# RAK3162_SX1262.net
KiCad netlist of a schematic drawn in Altium Designer
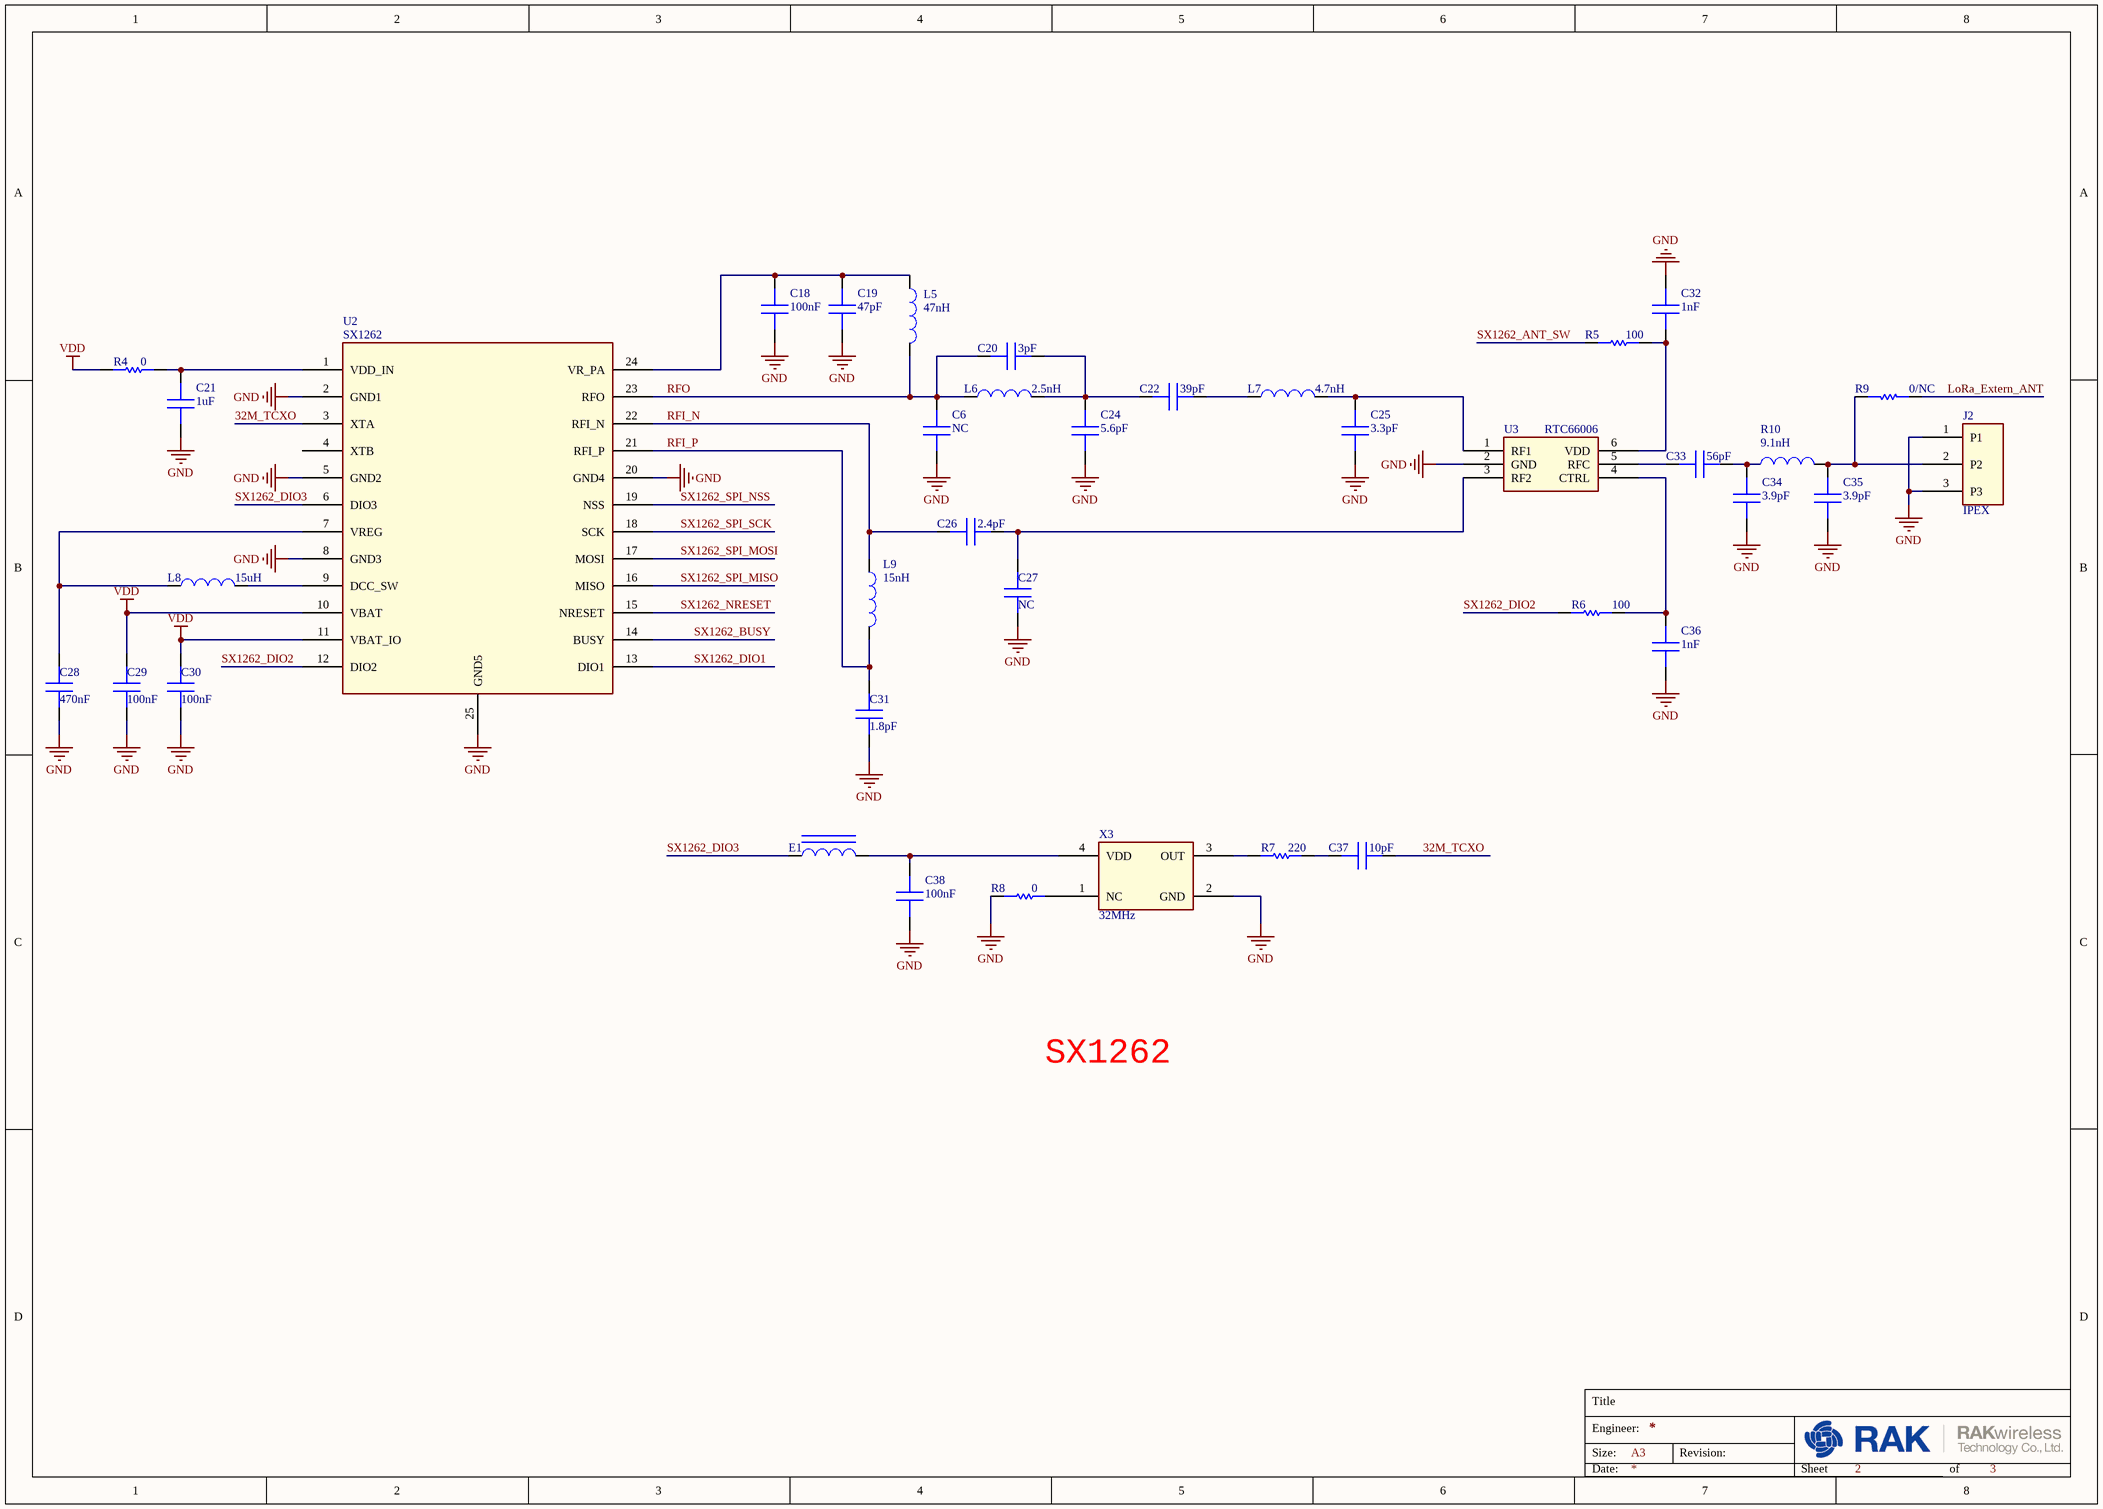
[diagram p0: RAK3162_SX1262.SchDoc]

(export (version "E")
  (design (tool "Eeschema 10.0.6"))
  (components
    (comp (ref "C6")
      (value "NC")
      (footprint "sc0201")
      (description "Capacitor-50V-5.6pF-±0.25pF-COG-0201")
      (fields (field (name "MANUFACTURER") "MURATA") (field (name "TOLERANCE") "±0.25pF"))
      (libsource (lib "RAK_Database_Lib_2022") (part "CAPACITOR NP"))
    )
    (comp (ref "C18")
      (value "100nF")
      (footprint "sc0201")
      (description "Capacitor-6.3V-100nF-±10%-X5R-0201")
      (fields (field (name "MANUFACTURER") "YAGEO") (field (name "TOLERANCE") "±10%"))
      (libsource (lib "RAK_Database_Lib_2022") (part "CAPACITOR NP"))
    )
    (comp (ref "C19")
      (value "47pF")
      (footprint "sc0201")
      (description "Capacitor-25V-47pF-±5%-NPO-0201")
      (fields (field (name "MANUFACTURER") "YAGEO") (field (name "TOLERANCE") "±5%"))
      (libsource (lib "RAK_Database_Lib_2022") (part "CAPACITOR NP"))
    )
    (comp (ref "C20")
      (value "3pF")
      (footprint "sc0201")
      (description "Capacitor-50V-3pF-±0.25pF-NPO-0201")
      (fields (field (name "MANUFACTURER") "YAGEO") (field (name "TOLERANCE") "±0.25pF"))
      (libsource (lib "RAK_Database_Lib_2022") (part "CAPACITOR NP"))
    )
    (comp (ref "C21")
      (value "1uF")
      (footprint "sc0201")
      (description "Capacitor-6.3V-1uF-±20%-X5R-0201")
      (fields (field (name "MANUFACTURER") "YAGEO") (field (name "TOLERANCE") "±20%"))
      (libsource (lib "RAK_Database_Lib_2022") (part "CAPACITOR NP"))
    )
    (comp (ref "C22")
      (value "39pF")
      (footprint "sc0201")
      (description "Capacitor-25V-39pF-±5%-NPO-0201")
      (fields (field (name "MANUFACTURER") "YAGEO") (field (name "TOLERANCE") "±5%"))
      (libsource (lib "RAK_Database_Lib_2022") (part "CAPACITOR NP"))
    )
    (comp (ref "C24")
      (value "5.6pF")
      (footprint "sc0201")
      (description "Capacitor-50V-5.6pF-±0.25pF-COG-0201")
      (fields (field (name "MANUFACTURER") "MURATA") (field (name "TOLERANCE") "±0.25pF"))
      (libsource (lib "RAK_Database_Lib_2022") (part "CAPACITOR NP"))
    )
    (comp (ref "C25")
      (value "3.3pF")
      (footprint "sc0201")
      (description "Capacitor-50V-3.3pF-±0.25pF-NPO-0201")
      (fields (field (name "MANUFACTURER") "YAGEO") (field (name "TOLERANCE") "±0.25pF"))
      (libsource (lib "RAK_Database_Lib_2022") (part "CAPACITOR NP"))
    )
    (comp (ref "C26")
      (value "2.4pF")
      (footprint "sc0201")
      (description "Capacitor-50V-2.4pF-±0.25pF-NPO-0201")
      (fields (field (name "MANUFACTURER") "YAGEO") (field (name "TOLERANCE") "±0.25pF"))
      (libsource (lib "RAK_Database_Lib_2022") (part "CAPACITOR NP"))
    )
    (comp (ref "C27")
      (value "NC")
      (footprint "sc0201")
      (description "Capacitor-25V-47pF-±5%-NPO-0201")
      (fields (field (name "MANUFACTURER") "YAGEO") (field (name "TOLERANCE") "±5%"))
      (libsource (lib "RAK_Database_Lib_2022") (part "CAPACITOR NP"))
    )
    (comp (ref "C28")
      (value "470nF")
      (footprint "sc0201")
      (description "Capacitor-6.3V-470nF-±20%-X5R-0201")
      (fields (field (name "MANUFACTURER") "MURATA") (field (name "TOLERANCE") "±20%"))
      (libsource (lib "RAK_Database_Lib_2022") (part "CAPACITOR NP"))
    )
    (comp (ref "C29")
      (value "100nF")
      (footprint "sc0201")
      (description "Capacitor-6.3V-100nF-±10%-X5R-0201")
      (fields (field (name "MANUFACTURER") "YAGEO") (field (name "TOLERANCE") "±10%"))
      (libsource (lib "RAK_Database_Lib_2022") (part "CAPACITOR NP"))
    )
    (comp (ref "C30")
      (value "100nF")
      (footprint "sc0201")
      (description "Capacitor-6.3V-100nF-±10%-X5R-0201")
      (fields (field (name "MANUFACTURER") "YAGEO") (field (name "TOLERANCE") "±10%"))
      (libsource (lib "RAK_Database_Lib_2022") (part "CAPACITOR NP"))
    )
    (comp (ref "C31")
      (value "1.8pF")
      (footprint "sc0201")
      (description "Capacitor-50V-1.8pF-±0.25pF-NPO-0201")
      (fields (field (name "MANUFACTURER") "YAGEO") (field (name "TOLERANCE") "±0.25pF"))
      (libsource (lib "RAK_Database_Lib_2022") (part "CAPACITOR NP"))
    )
    (comp (ref "C32")
      (value "1nF")
      (footprint "sc0201")
      (description "Capacitor-25V-1nF-±10%-X7R-0201")
      (fields (field (name "MANUFACTURER") "YAGEO") (field (name "TOLERANCE") "±10%"))
      (libsource (lib "RAK_Database_Lib_2022") (part "CAPACITOR NP"))
    )
    (comp (ref "C33")
      (value "56pF")
      (footprint "sc0201")
      (description "Capacitor-25V-56pF-±5%-NPO-0201")
      (fields (field (name "MANUFACTURER") "华新科技(WALSIN)") (field (name "TOLERANCE") "±5%"))
      (libsource (lib "RAK_Database_Lib_2022") (part "CAPACITOR NP"))
    )
    (comp (ref "C34")
      (value "3.9pF")
      (footprint "sc0201")
      (description "Capacitor-50V-3.9pF-±0.25pF-NPO-0201")
      (fields (field (name "MANUFACTURER") "YAGEO") (field (name "TOLERANCE") "±0.25pF"))
      (libsource (lib "RAK_Database_Lib_2022") (part "CAPACITOR NP"))
    )
    (comp (ref "C35")
      (value "3.9pF")
      (footprint "sc0201")
      (description "Capacitor-50V-3.9pF-±0.25pF-NPO-0201")
      (fields (field (name "MANUFACTURER") "YAGEO") (field (name "TOLERANCE") "±0.25pF"))
      (libsource (lib "RAK_Database_Lib_2022") (part "CAPACITOR NP"))
    )
    (comp (ref "C36")
      (value "1nF")
      (footprint "sc0201")
      (description "Capacitor-25V-1nF-±10%-X7R-0201")
      (fields (field (name "MANUFACTURER") "YAGEO") (field (name "TOLERANCE") "±10%"))
      (libsource (lib "RAK_Database_Lib_2022") (part "CAPACITOR NP"))
    )
    (comp (ref "C37")
      (value "10pF")
      (footprint "sc0201")
      (description "Capacitor-50V-10pF-±5%-NPO-0201")
      (fields (field (name "MANUFACTURER") "YAGEO") (field (name "TOLERANCE") "±5%"))
      (libsource (lib "RAK_Database_Lib_2022") (part "CAPACITOR NP"))
    )
    (comp (ref "C38")
      (value "100nF")
      (footprint "sc0201")
      (description "Capacitor-6.3V-100nF-±10%-X5R-0201")
      (fields (field (name "MANUFACTURER") "YAGEO") (field (name "TOLERANCE") "±10%"))
      (libsource (lib "RAK_Database_Lib_2022") (part "CAPACITOR NP"))
    )
    (comp (ref "E1")
      (value "BEAD")
      (footprint "SL0201")
      (description "EMI Ferrite Bead-240Ω±25%@100MHz-0.38Ω-350mA-0201")
      (fields (field (name "MANUFACTURER") "Murata") (field (name "PART NUMBER") "BLM03AX241SN1D"))
      (libsource (lib "RAK_Database_Lib_2022") (part "BEAD"))
    )
    (comp (ref "J2")
      (value "IPEX")
      (footprint "SCOXSMA_T")
      (description "Coaxial Connectors-IPEX MHF1-Receptacle, Male Pin-50Ohm-Surface Mount")
      (fields (field (name "MANUFACTURER") "BLDZ01") (field (name "PART_NUMBER") "ECT818000071"))
      (libsource (lib "RAK_Database_Lib_2022") (part "UFL"))
    )
    (comp (ref "L5")
      (value "47nH")
      (footprint "SL0402")
      (description "Inductor-47nH-±2%-1.15Ω-250mA-0402")
      (fields (field (name "MANUFACTURER") "MURATA") (field (name "PART NUMBER") "LQG15HN47NG02"))
      (libsource (lib "RAK_Database_Lib_2022") (part "INDUCTOR"))
    )
    (comp (ref "L6")
      (value "2.5nH")
      (footprint "sl0201")
      (description "Inductor-2.5nH-±0.1nH-0.2Ω-500mA-0201")
      (fields (field (name "MANUFACTURER") "MURATA") (field (name "PART NUMBER") "LQP03TN2N5B02"))
      (libsource (lib "RAK_Database_Lib_2022") (part "INDUCTOR"))
    )
    (comp (ref "L7")
      (value "4.7nH")
      (footprint "sl0201")
      (description "Inductor-4.7nH-±5%-0.4Ω-350mA-0201")
      (fields (field (name "MANUFACTURER") "MURATA") (field (name "PART NUMBER") "LQP03TN4N7J02D"))
      (libsource (lib "RAK_Database_Lib_2022") (part "INDUCTOR"))
    )
    (comp (ref "L8")
      (value "15uH")
      (footprint "SL0805")
      (description "Inductor-15uH-±20%-0.95Ω±30%-250mA-0805")
      (fields (field (name "MANUFACTURER") "TDK") (field (name "PART NUMBER") "MLZ2012M150WT000"))
      (libsource (lib "RAK_Database_Lib_2022") (part "INDUCTOR"))
    )
    (comp (ref "L9")
      (value "15nH")
      (footprint "sl0201")
      (description "Inductor-15nH-±5%-0.7Ω-250mA-0201")
      (fields (field (name "MANUFACTURER") "MURATA") (field (name "PART NUMBER") "LQP03TN15NJ02D"))
      (libsource (lib "RAK_Database_Lib_2022") (part "INDUCTOR"))
    )
    (comp (ref "R4")
      (value "0")
      (footprint "sr0201")
      (description "Resistor-0Ω-0.5A-50mΩMAX-0201")
      (fields (field (name "MANUFACTURER") "YAGEO") (field (name "PART NUMBER") "RC0201JR-070RL"))
      (libsource (lib "RAK_Database_Lib_2022") (part "RESISTOR"))
    )
    (comp (ref "R5")
      (value "100")
      (footprint "sr0201")
      (description "Resistor-1/20W-100Ω-±1%-0201")
      (fields (field (name "MANUFACTURER") "YAGEO") (field (name "PART NUMBER") "RC0201FR-07100RL"))
      (libsource (lib "RAK_Database_Lib_2022") (part "RESISTOR"))
    )
    (comp (ref "R6")
      (value "100")
      (footprint "sr0201")
      (description "Resistor-1/20W-100Ω-±1%-0201")
      (fields (field (name "MANUFACTURER") "YAGEO") (field (name "PART NUMBER") "RC0201FR-07100RL"))
      (libsource (lib "RAK_Database_Lib_2022") (part "RESISTOR"))
    )
    (comp (ref "R7")
      (value "220")
      (footprint "sr0201")
      (description "Resistor-1/20W-220Ω-±1%-0201")
      (fields (field (name "MANUFACTURER") "YAGEO") (field (name "PART NUMBER") "RC0201FR07-220RL"))
      (libsource (lib "RAK_Database_Lib_2022") (part "RESISTOR"))
    )
    (comp (ref "R8")
      (value "0")
      (footprint "sr0201")
      (description "Resistor-0Ω-0.5A-50mΩMAX-0201")
      (fields (field (name "MANUFACTURER") "YAGEO") (field (name "PART NUMBER") "RC0201JR-070RL"))
      (libsource (lib "RAK_Database_Lib_2022") (part "RESISTOR"))
    )
    (comp (ref "R9")
      (value "0/NC")
      (footprint "sr0201")
      (description "Resistor-0Ω-0.5A-50mΩMAX-0201")
      (fields (field (name "MANUFACTURER") "YAGEO") (field (name "PART NUMBER") "RC0201JR-070RL"))
      (libsource (lib "RAK_Database_Lib_2022") (part "RESISTOR"))
    )
    (comp (ref "R10")
      (value "9.1nH")
      (footprint "sl0201")
      (description "Inductor-9.1nH-±3%-0.7Ω-250mA-0201")
      (fields (field (name "MANUFACTURER") "MURATA") (field (name "PART NUMBER") "LQP03TN9N1H02D"))
      (libsource (lib "RAK_Database_Lib_2022") (part "INDUCTOR"))
    )
    (comp (ref "U2")
      (value "SX1262")
      (footprint "VQFN24_4X4MM")
      (description "RF IC-LoRa Transceiver-SX1262IMLTRT-150~960 MHz-22dBm-SF5 to SF12-1.8~3.7V-QFN24-4x4mm")
      (fields (field (name "MANUFACTURER") "SEMTECH") (field (name "PART NUMBER") "SX1262IMLTRT"))
      (libsource (lib "RAK_Database_Lib_2022") (part "SX126X"))
    )
    (comp (ref "U3")
      (value "RTC66006")
      (footprint "SC-70-6")
      (description "RF IC-RF Switch-PE4259-10~3000 MHz-SPDT-0.35 dB-30dB-SC-70-6")
      (fields (field (name "MANUFACTURER") "PSEMI") (field (name "PART NUMBER") "PE4259"))
      (libsource (lib "RAK_Database_Lib_2022") (part "PE4259"))
    )
    (comp (ref "X3")
      (value "32MHz")
      (footprint "S0SC4-2016")
      (description "Oscillator-32MHz-TCXO-±2ppm--30℃~85℃-1.8V~3.3V-SMD-2016-4pin")
      (fields (field (name "MANUFACTURER") "NDK") (field (name "PART NUMBER") "END4263A"))
      (libsource (lib "RAK_Database_Lib_2022") (part "TCXO"))
    )
  )
  (nets
    (net (code "1") (name "/32M_TCXO") (class "Default")
      (node (ref "C37") (pin "2") (pinfunction "NEG_2") (pintype "passive"))
      (node (ref "U2") (pin "3") (pinfunction "XTA_3") (pintype "passive"))
    )
    (net (code "2") (name "/LoRa_Extern_ANT") (class "Default")
      (node (ref "R9") (pin "1") (pinfunction "1_1") (pintype "passive"))
    )
    (net (code "3") (name "/RFI_N") (class "Default")
      (node (ref "C26") (pin "1") (pinfunction "POS_1") (pintype "passive"))
      (node (ref "L9") (pin "1") (pinfunction "1_1") (pintype "passive"))
      (node (ref "U2") (pin "22") (pinfunction "RFI_N_22") (pintype "passive"))
    )
    (net (code "4") (name "/RFI_P") (class "Default")
      (node (ref "C31") (pin "2") (pinfunction "NEG_2") (pintype "passive"))
      (node (ref "L9") (pin "2") (pinfunction "2_2") (pintype "passive"))
      (node (ref "U2") (pin "21") (pinfunction "RFI_P_21") (pintype "passive"))
    )
    (net (code "5") (name "/RFO") (class "Default")
      (node (ref "C20") (pin "1") (pinfunction "POS_1") (pintype "passive"))
      (node (ref "C6") (pin "2") (pinfunction "NEG_2") (pintype "passive"))
      (node (ref "L5") (pin "2") (pinfunction "2_2") (pintype "passive"))
      (node (ref "L6") (pin "1") (pinfunction "1_1") (pintype "passive"))
      (node (ref "U2") (pin "23") (pinfunction "RFO_23") (pintype "passive"))
    )
    (net (code "6") (name "/SX1262_ANT_SW") (class "Default")
      (node (ref "R5") (pin "2") (pinfunction "2_2") (pintype "passive"))
    )
    (net (code "7") (name "/SX1262_BUSY") (class "Default")
      (node (ref "U2") (pin "14") (pinfunction "BUSY_14") (pintype "passive"))
    )
    (net (code "8") (name "/SX1262_DIO1") (class "Default")
      (node (ref "U2") (pin "13") (pinfunction "DIO1_13") (pintype "passive"))
    )
    (net (code "9") (name "/SX1262_DIO2") (class "Default")
      (node (ref "R6") (pin "2") (pinfunction "2_2") (pintype "passive"))
      (node (ref "U2") (pin "12") (pinfunction "DIO2_12") (pintype "passive"))
    )
    (net (code "10") (name "/SX1262_DIO3") (class "Default")
      (node (ref "E1") (pin "1") (pinfunction "1_1") (pintype "passive"))
      (node (ref "U2") (pin "6") (pinfunction "DIO3_6") (pintype "passive"))
    )
    (net (code "11") (name "/SX1262_NRESET") (class "Default")
      (node (ref "U2") (pin "15") (pinfunction "NRESET_15") (pintype "passive"))
    )
    (net (code "12") (name "/SX1262_SPI_MISO") (class "Default")
      (node (ref "U2") (pin "16") (pinfunction "MISO_16") (pintype "passive"))
    )
    (net (code "13") (name "/SX1262_SPI_MOSI") (class "Default")
      (node (ref "U2") (pin "17") (pinfunction "MOSI_17") (pintype "passive"))
    )
    (net (code "14") (name "/SX1262_SPI_NSS") (class "Default")
      (node (ref "U2") (pin "19") (pinfunction "NSS_19") (pintype "passive"))
    )
    (net (code "15") (name "/SX1262_SPI_SCK") (class "Default")
      (node (ref "U2") (pin "18") (pinfunction "SCK_18") (pintype "passive"))
    )
    (net (code "16") (name "GND") (class "Default")
      (node (ref "C18") (pin "1") (pinfunction "POS_1") (pintype "passive"))
      (node (ref "C19") (pin "1") (pinfunction "POS_1") (pintype "passive"))
      (node (ref "C21") (pin "1") (pinfunction "POS_1") (pintype "passive"))
      (node (ref "C24") (pin "1") (pinfunction "POS_1") (pintype "passive"))
      (node (ref "C25") (pin "1") (pinfunction "POS_1") (pintype "passive"))
      (node (ref "C27") (pin "1") (pinfunction "POS_1") (pintype "passive"))
      (node (ref "C28") (pin "1") (pinfunction "POS_1") (pintype "passive"))
      (node (ref "C29") (pin "1") (pinfunction "POS_1") (pintype "passive"))
      (node (ref "C30") (pin "1") (pinfunction "POS_1") (pintype "passive"))
      (node (ref "C31") (pin "1") (pinfunction "POS_1") (pintype "passive"))
      (node (ref "C32") (pin "2") (pinfunction "NEG_2") (pintype "passive"))
      (node (ref "C34") (pin "1") (pinfunction "POS_1") (pintype "passive"))
      (node (ref "C35") (pin "1") (pinfunction "POS_1") (pintype "passive"))
      (node (ref "C36") (pin "1") (pinfunction "POS_1") (pintype "passive"))
      (node (ref "C38") (pin "1") (pinfunction "POS_1") (pintype "passive"))
      (node (ref "C6") (pin "1") (pinfunction "POS_1") (pintype "passive"))
      (node (ref "J2") (pin "1") (pinfunction "P1_1") (pintype "passive"))
      (node (ref "J2") (pin "3") (pinfunction "P3_3") (pintype "passive"))
      (node (ref "R8") (pin "2") (pinfunction "2_2") (pintype "passive"))
      (node (ref "U2") (pin "2") (pinfunction "GND1_2") (pintype "passive"))
      (node (ref "U2") (pin "20") (pinfunction "GND4_20") (pintype "passive"))
      (node (ref "U2") (pin "25") (pinfunction "GND5_25") (pintype "passive"))
      (node (ref "U2") (pin "5") (pinfunction "GND2_5") (pintype "passive"))
      (node (ref "U2") (pin "8") (pinfunction "GND3_8") (pintype "passive"))
      (node (ref "U3") (pin "2") (pinfunction "GND_2") (pintype "passive"))
      (node (ref "X3") (pin "2") (pinfunction "GND_2") (pintype "passive"))
    )
    (net (code "17") (name "Net-(C18-NEG)") (class "Default")
      (node (ref "C18") (pin "2") (pinfunction "NEG_2") (pintype "passive"))
      (node (ref "C19") (pin "2") (pinfunction "NEG_2") (pintype "passive"))
      (node (ref "L5") (pin "1") (pinfunction "1_1") (pintype "passive"))
      (node (ref "U2") (pin "24") (pinfunction "VR_PA_24") (pintype "passive"))
    )
    (net (code "18") (name "Net-(C20-NEG)") (class "Default")
      (node (ref "C20") (pin "2") (pinfunction "NEG_2") (pintype "passive"))
      (node (ref "C22") (pin "1") (pinfunction "POS_1") (pintype "passive"))
      (node (ref "C24") (pin "2") (pinfunction "NEG_2") (pintype "passive"))
      (node (ref "L6") (pin "2") (pinfunction "2_2") (pintype "passive"))
    )
    (net (code "19") (name "Net-(C21-NEG)") (class "Default")
      (node (ref "C21") (pin "2") (pinfunction "NEG_2") (pintype "passive"))
      (node (ref "R4") (pin "1") (pinfunction "1_1") (pintype "passive"))
      (node (ref "U2") (pin "1") (pinfunction "VDD_IN_1") (pintype "passive"))
    )
    (net (code "20") (name "Net-(C22-NEG)") (class "Default")
      (node (ref "C22") (pin "2") (pinfunction "NEG_2") (pintype "passive"))
      (node (ref "L7") (pin "1") (pinfunction "1_1") (pintype "passive"))
    )
    (net (code "21") (name "Net-(C25-NEG)") (class "Default")
      (node (ref "C25") (pin "2") (pinfunction "NEG_2") (pintype "passive"))
      (node (ref "L7") (pin "2") (pinfunction "2_2") (pintype "passive"))
      (node (ref "U3") (pin "1") (pinfunction "RF1_1") (pintype "passive"))
    )
    (net (code "22") (name "Net-(C26-NEG)") (class "Default")
      (node (ref "C26") (pin "2") (pinfunction "NEG_2") (pintype "passive"))
      (node (ref "C27") (pin "2") (pinfunction "NEG_2") (pintype "passive"))
      (node (ref "U3") (pin "3") (pinfunction "RF2_3") (pintype "passive"))
    )
    (net (code "23") (name "Net-(C28-NEG)") (class "Default")
      (node (ref "C28") (pin "2") (pinfunction "NEG_2") (pintype "passive"))
      (node (ref "L8") (pin "1") (pinfunction "1_1") (pintype "passive"))
      (node (ref "U2") (pin "7") (pinfunction "VREG_7") (pintype "passive"))
    )
    (net (code "24") (name "Net-(C32-POS)") (class "Default")
      (node (ref "C32") (pin "1") (pinfunction "POS_1") (pintype "passive"))
      (node (ref "R5") (pin "1") (pinfunction "1_1") (pintype "passive"))
      (node (ref "U3") (pin "6") (pinfunction "VDD_6") (pintype "passive"))
    )
    (net (code "25") (name "Net-(C33-NEG)") (class "Default")
      (node (ref "C33") (pin "2") (pinfunction "NEG_2") (pintype "passive"))
      (node (ref "C34") (pin "2") (pinfunction "NEG_2") (pintype "passive"))
      (node (ref "R10") (pin "1") (pinfunction "1_1") (pintype "passive"))
    )
    (net (code "26") (name "Net-(C33-POS)") (class "Default")
      (node (ref "C33") (pin "1") (pinfunction "POS_1") (pintype "passive"))
      (node (ref "U3") (pin "5") (pinfunction "RFC_5") (pintype "passive"))
    )
    (net (code "27") (name "Net-(C35-NEG)") (class "Default")
      (node (ref "C35") (pin "2") (pinfunction "NEG_2") (pintype "passive"))
      (node (ref "J2") (pin "2") (pinfunction "P2_2") (pintype "passive"))
      (node (ref "R10") (pin "2") (pinfunction "2_2") (pintype "passive"))
      (node (ref "R9") (pin "2") (pinfunction "2_2") (pintype "passive"))
    )
    (net (code "28") (name "Net-(C36-NEG)") (class "Default")
      (node (ref "C36") (pin "2") (pinfunction "NEG_2") (pintype "passive"))
      (node (ref "R6") (pin "1") (pinfunction "1_1") (pintype "passive"))
      (node (ref "U3") (pin "4") (pinfunction "CTRL_4") (pintype "passive"))
    )
    (net (code "29") (name "Net-(C37-POS)") (class "Default")
      (node (ref "C37") (pin "1") (pinfunction "POS_1") (pintype "passive"))
      (node (ref "R7") (pin "1") (pinfunction "1_1") (pintype "passive"))
    )
    (net (code "30") (name "Net-(C38-NEG)") (class "Default")
      (node (ref "C38") (pin "2") (pinfunction "NEG_2") (pintype "passive"))
      (node (ref "E1") (pin "2") (pinfunction "2_2") (pintype "passive"))
      (node (ref "X3") (pin "4") (pinfunction "VDD_4") (pintype "passive"))
    )
    (net (code "31") (name "Net-(U2-DCC_SW)") (class "Default")
      (node (ref "L8") (pin "2") (pinfunction "2_2") (pintype "passive"))
      (node (ref "U2") (pin "9") (pinfunction "DCC_SW_9") (pintype "passive"))
    )
    (net (code "32") (name "Net-(X3-NC)") (class "Default")
      (node (ref "R8") (pin "1") (pinfunction "1_1") (pintype "passive"))
      (node (ref "X3") (pin "1") (pinfunction "NC_1") (pintype "passive"))
    )
    (net (code "33") (name "Net-(X3-OUT)") (class "Default")
      (node (ref "R7") (pin "2") (pinfunction "2_2") (pintype "passive"))
      (node (ref "X3") (pin "3") (pinfunction "OUT_3") (pintype "passive"))
    )
    (net (code "34") (name "VDD") (class "Default")
      (node (ref "C29") (pin "2") (pinfunction "NEG_2") (pintype "passive"))
      (node (ref "C30") (pin "2") (pinfunction "NEG_2") (pintype "passive"))
      (node (ref "R4") (pin "2") (pinfunction "2_2") (pintype "passive"))
      (node (ref "U2") (pin "10") (pinfunction "VBAT_10") (pintype "passive"))
      (node (ref "U2") (pin "11") (pinfunction "VBAT_IO_11") (pintype "passive"))
    )
    (net (code "35") (name "unconnected-(U2-XTB-Pad4)") (class "Default")
      (node (ref "U2") (pin "4") (pinfunction "XTB_4") (pintype "passive"))
    )
  )
)
